# FTDI_RS232.net
KiCad netlist of a schematic drawn in EAGLE
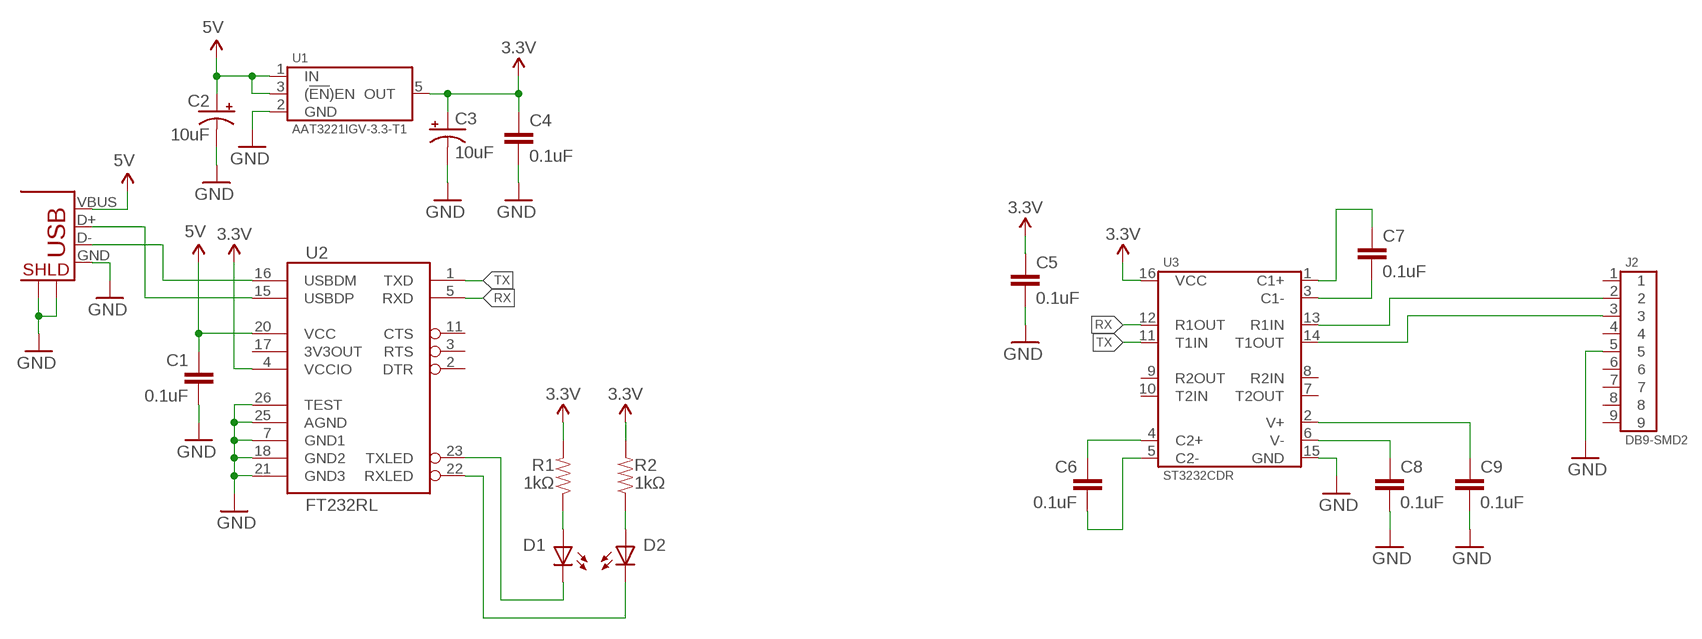
[diagram p0: schematic, sheet 1]

(export (version "E")
  (design (tool "Eeschema 10.0.6"))
  (components
    (comp (ref "C1")
      (value "0.1uF")
      (footprint "eagle-import:0805")
      (libsource (lib "eagle-import") (part "CAP0805"))
    )
    (comp (ref "C2")
      (value "10uF")
      (footprint "eagle-import:0805-CAP_POL")
      (libsource (lib "eagle-import") (part "CAP_POL0805"))
    )
    (comp (ref "C3")
      (value "10uF")
      (footprint "eagle-import:0805-CAP_POL")
      (libsource (lib "eagle-import") (part "CAP_POL0805"))
    )
    (comp (ref "C4")
      (value "0.1uF")
      (footprint "eagle-import:0805")
      (libsource (lib "eagle-import") (part "CAP0805"))
    )
    (comp (ref "C5")
      (value "0.1uF")
      (footprint "eagle-import:0805")
      (libsource (lib "eagle-import") (part "CAP0805"))
    )
    (comp (ref "C6")
      (value "0.1uF")
      (footprint "eagle-import:0805")
      (libsource (lib "eagle-import") (part "CAP0805"))
    )
    (comp (ref "C7")
      (value "0.1uF")
      (footprint "eagle-import:0805")
      (libsource (lib "eagle-import") (part "CAP0805"))
    )
    (comp (ref "C8")
      (value "0.1uF")
      (footprint "eagle-import:0805")
      (libsource (lib "eagle-import") (part "CAP0805"))
    )
    (comp (ref "C9")
      (value "0.1uF")
      (footprint "eagle-import:0805")
      (libsource (lib "eagle-import") (part "CAP0805"))
    )
    (comp (ref "D1")
      (value "LED-0805")
      (footprint "eagle-import:0805-LED")
      (libsource (lib "eagle-import") (part "LED-0805"))
    )
    (comp (ref "D2")
      (value "LED-0805")
      (footprint "eagle-import:0805-LED")
      (libsource (lib "eagle-import") (part "LED-0805"))
    )
    (comp (ref "J1")
      (value "USB+SHIELD")
      (footprint "eagle-import:USB-B-PTH")
      (libsource (lib "eagle-import") (part "USB+SHIELD"))
    )
    (comp (ref "J2")
      (value "DB9-SMD2")
      (footprint "eagle-import:DB9_SMD2")
      (libsource (lib "eagle-import") (part "DB9-SMD2"))
    )
    (comp (ref "R1")
      (value "1kΩ")
      (footprint "eagle-import:0805-RES")
      (libsource (lib "eagle-import") (part "RESISTOR-0805"))
    )
    (comp (ref "R2")
      (value "1kΩ")
      (footprint "eagle-import:0805-RES")
      (libsource (lib "eagle-import") (part "RESISTOR-0805"))
    )
    (comp (ref "U1")
      (value "AAT3221IGV-3.3-T1")
      (footprint "eagle-import:SOT23-5")
      (libsource (lib "eagle-import") (part "AAT3221IGV-3.3-T1"))
    )
    (comp (ref "U2")
      (value "FT232RL")
      (footprint "eagle-import:SSOP28DB")
      (libsource (lib "eagle-import") (part "FT232RL-BASICSSOP"))
    )
    (comp (ref "U3")
      (value "ST3232CDR")
      (footprint "eagle-import:SOIC-16")
      (libsource (lib "eagle-import") (part "ST3232CDR"))
    )
  )
  (nets
    (net (code "1") (name "3.3V") (class "Default")
      (node (ref "C3") (pin "A") (pinfunction "+_A") (pintype "passive"))
      (node (ref "C4") (pin "1") (pinfunction "1_1") (pintype "passive"))
      (node (ref "C5") (pin "1") (pinfunction "1_1") (pintype "passive"))
      (node (ref "R1") (pin "2") (pinfunction "2_2") (pintype "passive"))
      (node (ref "R2") (pin "2") (pinfunction "2_2") (pintype "passive"))
      (node (ref "U1") (pin "5") (pinfunction "OUT_5") (pintype "bidirectional"))
      (node (ref "U2") (pin "4") (pinfunction "VCCIO_4") (pintype "power_in"))
      (node (ref "U3") (pin "16") (pinfunction "VCC_16") (pintype "bidirectional"))
    )
    (net (code "2") (name "5V") (class "Default")
      (node (ref "C1") (pin "1") (pinfunction "1_1") (pintype "passive"))
      (node (ref "C2") (pin "A") (pinfunction "+_A") (pintype "passive"))
      (node (ref "J1") (pin "VBUS") (pinfunction "VBUS_VBUS") (pintype "bidirectional"))
      (node (ref "U1") (pin "1") (pinfunction "IN_1") (pintype "bidirectional"))
      (node (ref "U1") (pin "3") (pinfunction "(~{EN})EN_3") (pintype "bidirectional"))
      (node (ref "U2") (pin "20") (pinfunction "VCC_20") (pintype "power_in"))
    )
    (net (code "3") (name "GND") (class "Default")
      (node (ref "C1") (pin "2") (pinfunction "2_2") (pintype "passive"))
      (node (ref "C2") (pin "C") (pinfunction "-_C") (pintype "passive"))
      (node (ref "C3") (pin "C") (pinfunction "-_C") (pintype "passive"))
      (node (ref "C4") (pin "2") (pinfunction "2_2") (pintype "passive"))
      (node (ref "C5") (pin "2") (pinfunction "2_2") (pintype "passive"))
      (node (ref "C8") (pin "2") (pinfunction "2_2") (pintype "passive"))
      (node (ref "C9") (pin "2") (pinfunction "2_2") (pintype "passive"))
      (node (ref "J1") (pin "GND") (pinfunction "GND_GND") (pintype "bidirectional"))
      (node (ref "J1") (pin "S1") (pinfunction "P$1_S1") (pintype "bidirectional"))
      (node (ref "J1") (pin "S2") (pinfunction "P$2_S2") (pintype "bidirectional"))
      (node (ref "J2") (pin "5") (pinfunction "5_5") (pintype "bidirectional"))
      (node (ref "U1") (pin "2") (pinfunction "GND_2") (pintype "bidirectional"))
      (node (ref "U2") (pin "18") (pinfunction "GND2_18") (pintype "power_in"))
      (node (ref "U2") (pin "21") (pinfunction "GND3_21") (pintype "power_in"))
      (node (ref "U2") (pin "25") (pinfunction "AGND_25") (pintype "power_in"))
      (node (ref "U2") (pin "26") (pinfunction "TEST_26") (pintype "input"))
      (node (ref "U2") (pin "7") (pinfunction "GND1_7") (pintype "power_in"))
      (node (ref "U3") (pin "15") (pinfunction "GND_15") (pintype "bidirectional"))
    )
    (net (code "4") (name "Net-(D1-PadA)") (class "Default")
      (node (ref "D1") (pin "A") (pinfunction "A_A") (pintype "passive"))
      (node (ref "R1") (pin "1") (pinfunction "1_1") (pintype "passive"))
    )
    (net (code "5") (name "Net-(D2-PadA)") (class "Default")
      (node (ref "D2") (pin "A") (pinfunction "A_A") (pintype "passive"))
      (node (ref "R2") (pin "1") (pinfunction "1_1") (pintype "passive"))
    )
    (net (code "6") (name "Net-(U2-RXLED)") (class "Default")
      (node (ref "D2") (pin "C") (pinfunction "C_C") (pintype "passive"))
      (node (ref "U2") (pin "22") (pinfunction "RXLED_22") (pintype "bidirectional"))
    )
    (net (code "7") (name "Net-(U2-TXLED)") (class "Default")
      (node (ref "D1") (pin "C") (pinfunction "C_C") (pintype "passive"))
      (node (ref "U2") (pin "23") (pinfunction "TXLED_23") (pintype "bidirectional"))
    )
    (net (code "8") (name "Net-(U2-USBDM)") (class "Default")
      (node (ref "J1") (pin "D-") (pinfunction "D-_D-") (pintype "bidirectional"))
      (node (ref "U2") (pin "16") (pinfunction "USBDM_16") (pintype "bidirectional"))
    )
    (net (code "9") (name "Net-(U2-USBDP)") (class "Default")
      (node (ref "J1") (pin "D+") (pinfunction "D+_D+") (pintype "bidirectional"))
      (node (ref "U2") (pin "15") (pinfunction "USBDP_15") (pintype "bidirectional"))
    )
    (net (code "10") (name "Net-(U3-C1+)") (class "Default")
      (node (ref "C7") (pin "1") (pinfunction "1_1") (pintype "passive"))
      (node (ref "U3") (pin "1") (pinfunction "C1+_1") (pintype "bidirectional"))
    )
    (net (code "11") (name "Net-(U3-C1-)") (class "Default")
      (node (ref "C7") (pin "2") (pinfunction "2_2") (pintype "passive"))
      (node (ref "U3") (pin "3") (pinfunction "C1-_3") (pintype "bidirectional"))
    )
    (net (code "12") (name "Net-(U3-C2+)") (class "Default")
      (node (ref "C6") (pin "1") (pinfunction "1_1") (pintype "passive"))
      (node (ref "U3") (pin "4") (pinfunction "C2+_4") (pintype "bidirectional"))
    )
    (net (code "13") (name "Net-(U3-C2-)") (class "Default")
      (node (ref "C6") (pin "2") (pinfunction "2_2") (pintype "passive"))
      (node (ref "U3") (pin "5") (pinfunction "C2-_5") (pintype "bidirectional"))
    )
    (net (code "14") (name "Net-(U3-R1IN)") (class "Default")
      (node (ref "J2") (pin "2") (pinfunction "2_2") (pintype "bidirectional"))
      (node (ref "U3") (pin "13") (pinfunction "R1IN_13") (pintype "bidirectional"))
    )
    (net (code "15") (name "Net-(U3-T1OUT)") (class "Default")
      (node (ref "J2") (pin "3") (pinfunction "3_3") (pintype "bidirectional"))
      (node (ref "U3") (pin "14") (pinfunction "T1OUT_14") (pintype "bidirectional"))
    )
    (net (code "16") (name "Net-(U3-V+)") (class "Default")
      (node (ref "C9") (pin "1") (pinfunction "1_1") (pintype "passive"))
      (node (ref "U3") (pin "2") (pinfunction "V+_2") (pintype "bidirectional"))
    )
    (net (code "17") (name "Net-(U3-V-)") (class "Default")
      (node (ref "C8") (pin "1") (pinfunction "1_1") (pintype "passive"))
      (node (ref "U3") (pin "6") (pinfunction "V-_6") (pintype "bidirectional"))
    )
    (net (code "18") (name "RX") (class "Default")
      (node (ref "U2") (pin "5") (pinfunction "RXD_5") (pintype "input"))
      (node (ref "U3") (pin "12") (pinfunction "R1OUT_12") (pintype "bidirectional"))
    )
    (net (code "19") (name "TX") (class "Default")
      (node (ref "U2") (pin "1") (pinfunction "TXD_1") (pintype "output"))
      (node (ref "U3") (pin "11") (pinfunction "T1IN_11") (pintype "bidirectional"))
    )
    (net (code "20") (name "unconnected-(J2-Pad1)") (class "Default")
      (node (ref "J2") (pin "1") (pinfunction "1_1") (pintype "bidirectional"))
    )
    (net (code "21") (name "unconnected-(J2-Pad4)") (class "Default")
      (node (ref "J2") (pin "4") (pinfunction "4_4") (pintype "bidirectional"))
    )
    (net (code "22") (name "unconnected-(J2-Pad6)") (class "Default")
      (node (ref "J2") (pin "6") (pinfunction "6_6") (pintype "bidirectional"))
    )
    (net (code "23") (name "unconnected-(J2-Pad7)") (class "Default")
      (node (ref "J2") (pin "7") (pinfunction "7_7") (pintype "bidirectional"))
    )
    (net (code "24") (name "unconnected-(J2-Pad8)") (class "Default")
      (node (ref "J2") (pin "8") (pinfunction "8_8") (pintype "bidirectional"))
    )
    (net (code "25") (name "unconnected-(J2-Pad9)") (class "Default")
      (node (ref "J2") (pin "9") (pinfunction "9_9") (pintype "bidirectional"))
    )
    (net (code "26") (name "unconnected-(U2-3V3OUT-Pad17)") (class "Default")
      (node (ref "U2") (pin "17") (pinfunction "3V3OUT_17") (pintype "output"))
    )
    (net (code "27") (name "unconnected-(U2-CTS-Pad11)") (class "Default")
      (node (ref "U2") (pin "11") (pinfunction "CTS_11") (pintype "bidirectional"))
    )
    (net (code "28") (name "unconnected-(U2-DTR-Pad2)") (class "Default")
      (node (ref "U2") (pin "2") (pinfunction "DTR_2") (pintype "bidirectional"))
    )
    (net (code "29") (name "unconnected-(U2-RTS-Pad3)") (class "Default")
      (node (ref "U2") (pin "3") (pinfunction "RTS_3") (pintype "bidirectional"))
    )
    (net (code "30") (name "unconnected-(U3-R2IN-Pad8)") (class "Default")
      (node (ref "U3") (pin "8") (pinfunction "R2IN_8") (pintype "bidirectional"))
    )
    (net (code "31") (name "unconnected-(U3-R2OUT-Pad9)") (class "Default")
      (node (ref "U3") (pin "9") (pinfunction "R2OUT_9") (pintype "bidirectional"))
    )
    (net (code "32") (name "unconnected-(U3-T2IN-Pad10)") (class "Default")
      (node (ref "U3") (pin "10") (pinfunction "T2IN_10") (pintype "bidirectional"))
    )
    (net (code "33") (name "unconnected-(U3-T2OUT-Pad7)") (class "Default")
      (node (ref "U3") (pin "7") (pinfunction "T2OUT_7") (pintype "bidirectional"))
    )
  )
)
